# imu.net
KiCad netlist of a schematic drawn in Altium Designer
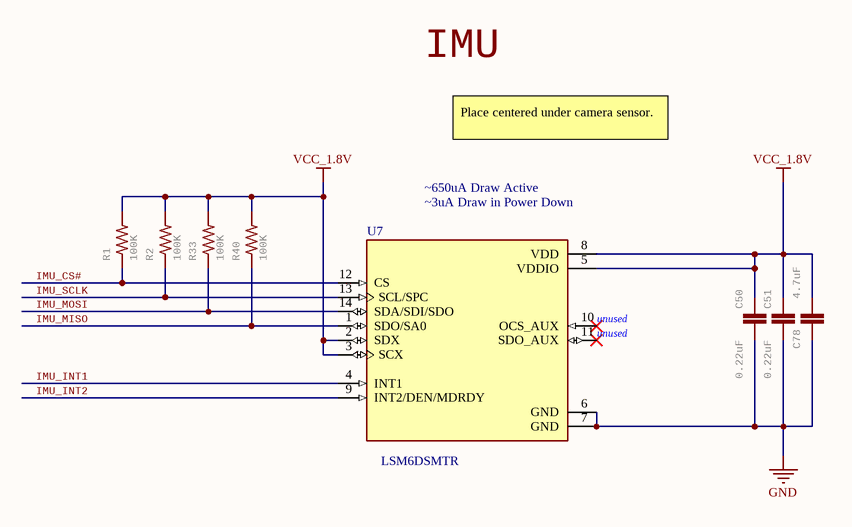
[diagram p0: imu.SchDoc]

(export (version "E")
  (design (tool "Eeschema 10.0.6"))
  (components
    (comp (ref "C50")
      (value "0.22uF")
      (footprint "C0201")
      (description "CAPACITOR, European symbol")
      (fields (field (name "MPN") "GRM033R60J224ME15D"))
      (libsource (lib "openmv-ae3") (part "C-EUC0201"))
    )
    (comp (ref "C51")
      (value "0.22uF")
      (footprint "C0201")
      (description "CAPACITOR, European symbol")
      (fields (field (name "MPN") "GRM033R60J224ME15D"))
      (libsource (lib "openmv-ae3") (part "C-EUC0201"))
    )
    (comp (ref "C78")
      (value "4.7uF")
      (footprint "0402-CAP")
      (description "0402 (1005 Metric) Nick Garner - TeleSense")
      (fields (field (name "MPN") "JMK105BBJ475MV-F"))
      (libsource (lib "openmv-ae3") (part "CAP_0402"))
    )
    (comp (ref "R1")
      (value "100K")
      (footprint "R0201")
      (fields (field (name "MPN") "RMCF0201FT100K") (field (name "LIBRARYNAME") "sfe"))
      (libsource (lib "openmv-ae3") (part "RESISTOR0402-RES"))
    )
    (comp (ref "R2")
      (value "100K")
      (footprint "R0201")
      (fields (field (name "MPN") "RMCF0201FT100K") (field (name "LIBRARYNAME") "sfe"))
      (libsource (lib "openmv-ae3") (part "RESISTOR0402-RES"))
    )
    (comp (ref "R33")
      (value "100K")
      (footprint "R0201")
      (fields (field (name "MPN") "RMCF0201FT100K") (field (name "LIBRARYNAME") "sfe"))
      (libsource (lib "openmv-ae3") (part "RESISTOR0402-RES"))
    )
    (comp (ref "R40")
      (value "100K")
      (footprint "R0201")
      (fields (field (name "MPN") "RMCF0201FT100K") (field (name "LIBRARYNAME") "sfe"))
      (libsource (lib "openmv-ae3") (part "RESISTOR0402-RES"))
    )
    (comp (ref "U7")
      (value "~")
      (footprint "LSM6DSMTR")
      (description "Accelerometer, Gyroscope, Temperature, 6 Axis Sensor IÂ²C, SPI Output")
      (fields
        (field (name "MF") "STMicroelectronics")
        (field (name "MP") "LSM6DSMTR")
        (field (name "MPN") "LSM6DSMTR")
      )
      (libsource (lib "openmv-ae3") (part "LSM6DSMTR"))
    )
  )
  (nets
    (net (code "1") (name "/IMU_CS#") (class "Default")
      (node (ref "R1") (pin "1") (pinfunction "1_1") (pintype "passive"))
      (node (ref "U7") (pin "12") (pinfunction "CS_12") (pintype "input"))
    )
    (net (code "2") (name "/IMU_INT1") (class "Default")
      (node (ref "U7") (pin "4") (pinfunction "INT1_4") (pintype "input"))
    )
    (net (code "3") (name "/IMU_INT2") (class "Default")
      (node (ref "U7") (pin "9") (pinfunction "INT2/DEN/MDRDY_9") (pintype "input"))
    )
    (net (code "4") (name "/IMU_MISO") (class "Default")
      (node (ref "R40") (pin "1") (pinfunction "1_1") (pintype "passive"))
      (node (ref "U7") (pin "1") (pinfunction "SDO/SA0_1") (pintype "bidirectional"))
    )
    (net (code "5") (name "/IMU_MOSI") (class "Default")
      (node (ref "R33") (pin "1") (pinfunction "1_1") (pintype "passive"))
      (node (ref "U7") (pin "14") (pinfunction "SDA/SDI/SDO_14") (pintype "bidirectional"))
    )
    (net (code "6") (name "/IMU_SCLK") (class "Default")
      (node (ref "R2") (pin "1") (pinfunction "1_1") (pintype "passive"))
      (node (ref "U7") (pin "13") (pinfunction "SCL/SPC_13") (pintype "input"))
    )
    (net (code "7") (name "GND") (class "Default")
      (node (ref "C50") (pin "2") (pinfunction "2_2") (pintype "passive"))
      (node (ref "C51") (pin "2") (pinfunction "2_2") (pintype "passive"))
      (node (ref "C78") (pin "1") (pinfunction "1_1") (pintype "passive"))
      (node (ref "U7") (pin "6") (pinfunction "GND_6") (pintype "power_in"))
      (node (ref "U7") (pin "7") (pinfunction "GND_7") (pintype "power_in"))
    )
    (net (code "8") (name "VCC_1.8V") (class "Default")
      (node (ref "C50") (pin "1") (pinfunction "1_1") (pintype "passive"))
      (node (ref "C51") (pin "1") (pinfunction "1_1") (pintype "passive"))
      (node (ref "C78") (pin "2") (pinfunction "2_2") (pintype "passive"))
      (node (ref "R1") (pin "2") (pinfunction "2_2") (pintype "passive"))
      (node (ref "R2") (pin "2") (pinfunction "2_2") (pintype "passive"))
      (node (ref "R33") (pin "2") (pinfunction "2_2") (pintype "passive"))
      (node (ref "R40") (pin "2") (pinfunction "2_2") (pintype "passive"))
      (node (ref "U7") (pin "2") (pinfunction "SDX_2") (pintype "bidirectional"))
      (node (ref "U7") (pin "3") (pinfunction "SCX_3") (pintype "bidirectional"))
      (node (ref "U7") (pin "5") (pinfunction "VDDIO_5") (pintype "power_in"))
      (node (ref "U7") (pin "8") (pinfunction "VDD_8") (pintype "power_in"))
    )
    (net (code "9") (name "unconnected-(U7-OCS_AUX-Pad10)") (class "Default")
      (node (ref "U7") (pin "10") (pinfunction "OCS_AUX_10") (pintype "input+no_connect"))
    )
    (net (code "10") (name "unconnected-(U7-SDO_AUX-Pad11)") (class "Default")
      (node (ref "U7") (pin "11") (pinfunction "SDO_AUX_11") (pintype "bidirectional+no_connect"))
    )
  )
)
